# DPT2_0.net
KiCad netlist of a schematic drawn in Altium Designer
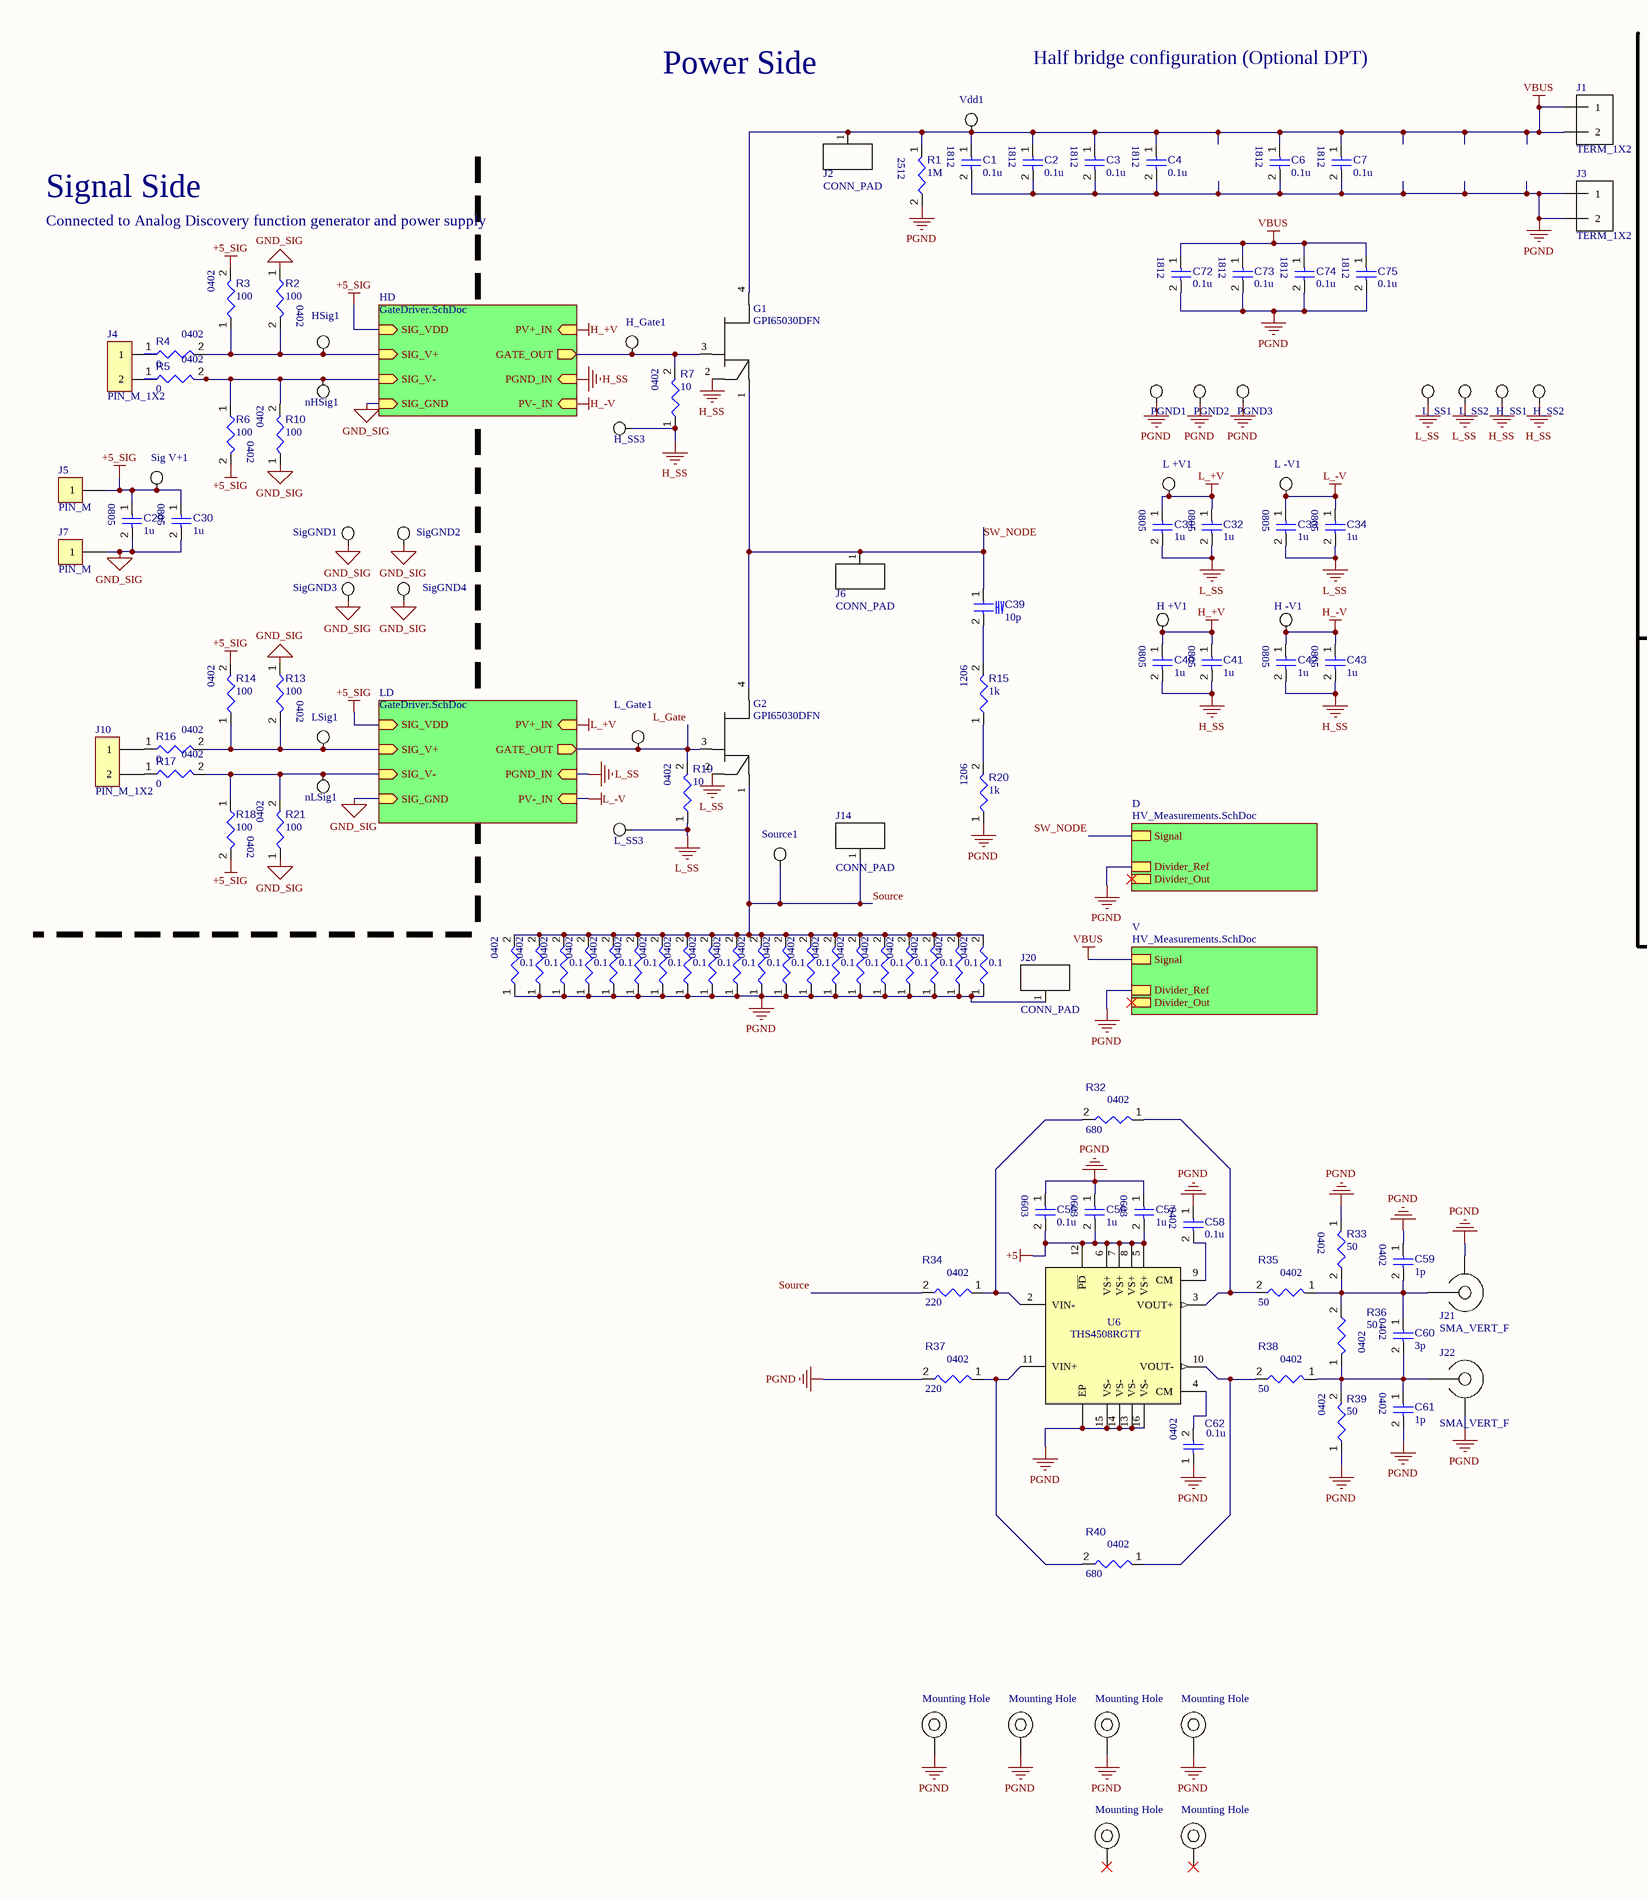
[diagram p0: DPT2.0.SchDoc, left]
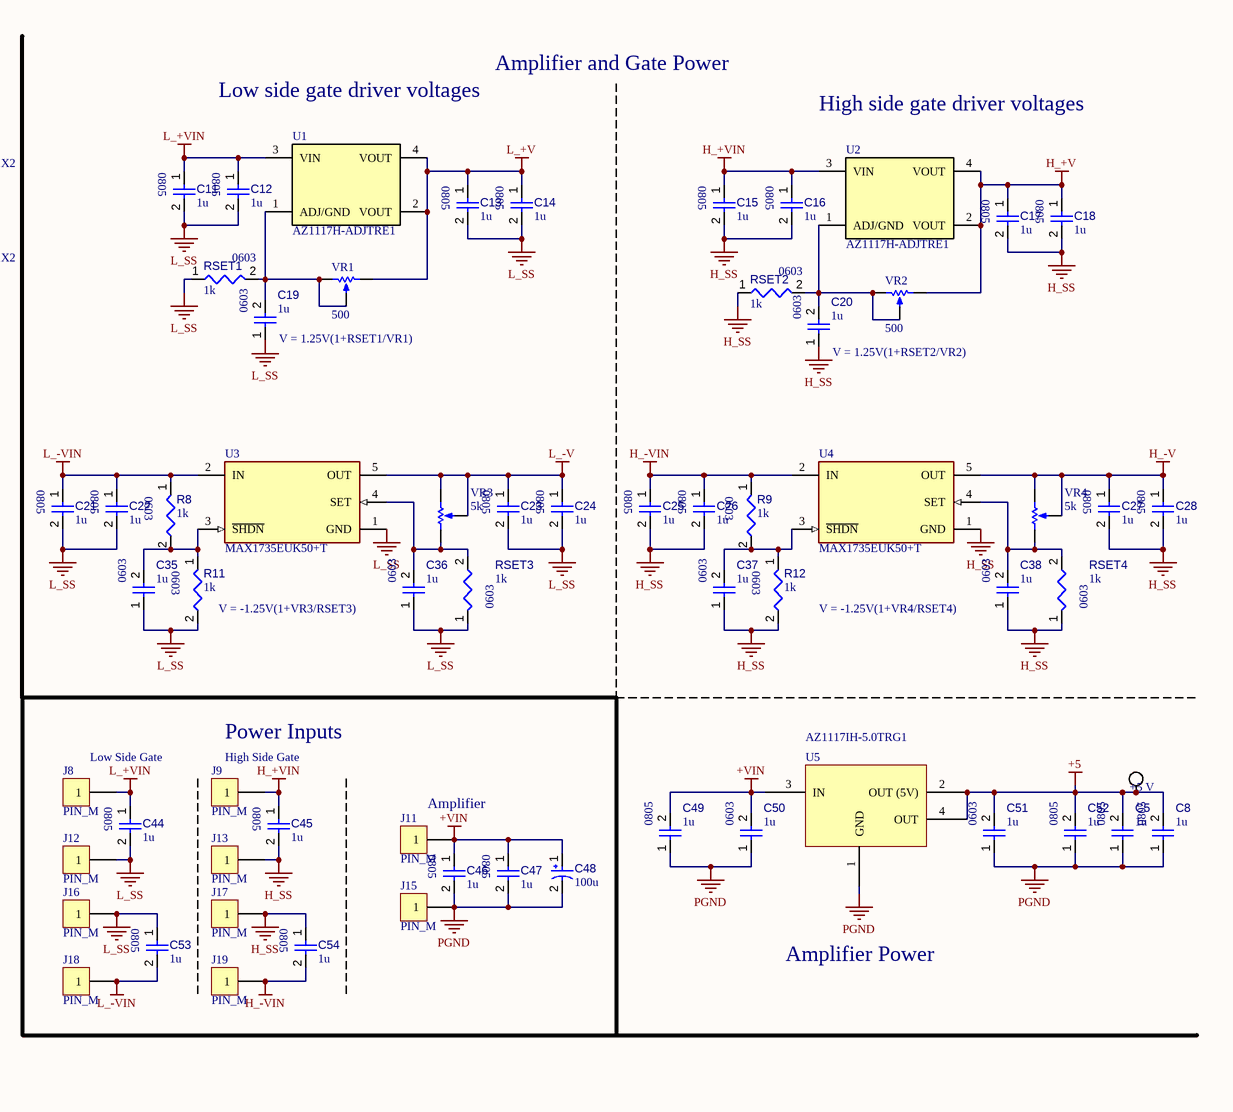
[diagram p1: DPT2.0.SchDoc, right]

(export (version "E")
  (design (tool "Eeschema 10.0.6"))
  (components
    (comp (ref "+5 V")
      (value "Testpoint")
      (footprint "Testpoint-Footprint-1")
      (description "testpoint for circuit")
      (libsource (lib "2256-GaN Power") (part "Testpoint-Symbol-1"))
    )
    (comp (ref "C1")
      (value "0.1u")
      (footprint "CAP_1812")
      (description "Non polarized SMD capacitor - 1812 (4532 Metric)")
      (fields (field (name "Comment") "CAP-1812"))
      (libsource (lib "2256-GaN Power") (part "CAP-NP-2"))
    )
    (comp (ref "C2")
      (value "0.1u")
      (footprint "CAP_1812")
      (description "Non polarized SMD capacitor - 1812 (4532 Metric)")
      (fields (field (name "Comment") "CAP-1812"))
      (libsource (lib "2256-GaN Power") (part "CAP-NP-2"))
    )
    (comp (ref "C3")
      (value "0.1u")
      (footprint "CAP_1812")
      (description "Non polarized SMD capacitor - 1812 (4532 Metric)")
      (fields (field (name "Comment") "CAP-1812"))
      (libsource (lib "2256-GaN Power") (part "CAP-NP-2"))
    )
    (comp (ref "C4")
      (value "0.1u")
      (footprint "CAP_1812")
      (description "Non polarized SMD capacitor - 1812 (4532 Metric)")
      (fields (field (name "Comment") "CAP-1812"))
      (libsource (lib "2256-GaN Power") (part "CAP-NP-2"))
    )
    (comp (ref "C5")
      (value "1u")
      (footprint "CAP_0805_MED")
      (description "Non polarized SMD capacitor - 0805 (1608 Metric)")
      (fields (field (name "Comment") "CAP-0805"))
      (libsource (lib "2256-GaN Power") (part "CAP-NP-2"))
    )
    (comp (ref "C6")
      (value "0.1u")
      (footprint "CAP_1812")
      (description "Non polarized SMD capacitor - 1812 (4532 Metric)")
      (fields (field (name "Comment") "CAP-1812"))
      (libsource (lib "2256-GaN Power") (part "CAP-NP-2"))
    )
    (comp (ref "C7")
      (value "0.1u")
      (footprint "CAP_1812")
      (description "Non polarized SMD capacitor - 1812 (4532 Metric)")
      (fields (field (name "Comment") "CAP-1812"))
      (libsource (lib "2256-GaN Power") (part "CAP-NP-2"))
    )
    (comp (ref "C8")
      (value "1u")
      (footprint "CAP_0805_MED")
      (description "Non polarized SMD capacitor - 0805 (1608 Metric)")
      (fields (field (name "Comment") "CAP-0805"))
      (libsource (lib "2256-GaN Power") (part "CAP-NP-2"))
    )
    (comp (ref "C11")
      (value "1u")
      (footprint "CAP_0805_MED")
      (description "Non polarized SMD capacitor - 0805 (1608 Metric)")
      (fields (field (name "Comment") "CAP-0805"))
      (libsource (lib "2256-GaN Power") (part "CAP-NP-2"))
    )
    (comp (ref "C12")
      (value "1u")
      (footprint "CAP_0805_MED")
      (description "Non polarized SMD capacitor - 0805 (1608 Metric)")
      (fields (field (name "Comment") "CAP-0805"))
      (libsource (lib "2256-GaN Power") (part "CAP-NP-2"))
    )
    (comp (ref "C13")
      (value "1u")
      (footprint "CAP_0805_MED")
      (description "Non polarized SMD capacitor - 0805 (1608 Metric)")
      (fields (field (name "Comment") "CAP-0805"))
      (libsource (lib "2256-GaN Power") (part "CAP-NP-2"))
    )
    (comp (ref "C14")
      (value "1u")
      (footprint "CAP_0805_MED")
      (description "Non polarized SMD capacitor - 0805 (1608 Metric)")
      (fields (field (name "Comment") "CAP-0805"))
      (libsource (lib "2256-GaN Power") (part "CAP-NP-2"))
    )
    (comp (ref "C15")
      (value "1u")
      (footprint "CAP_0805_MED")
      (description "Non polarized SMD capacitor - 0805 (1608 Metric)")
      (fields (field (name "Comment") "CAP-0805"))
      (libsource (lib "2256-GaN Power") (part "CAP-NP-2"))
    )
    (comp (ref "C16")
      (value "1u")
      (footprint "CAP_0805_MED")
      (description "Non polarized SMD capacitor - 0805 (1608 Metric)")
      (fields (field (name "Comment") "CAP-0805"))
      (libsource (lib "2256-GaN Power") (part "CAP-NP-2"))
    )
    (comp (ref "C17")
      (value "1u")
      (footprint "CAP_0805_MED")
      (description "Non polarized SMD capacitor - 0805 (1608 Metric)")
      (fields (field (name "Comment") "CAP-0805"))
      (libsource (lib "2256-GaN Power") (part "CAP-NP-2"))
    )
    (comp (ref "C18")
      (value "1u")
      (footprint "CAP_0805_MED")
      (description "Non polarized SMD capacitor - 0805 (1608 Metric)")
      (fields (field (name "Comment") "CAP-0805"))
      (libsource (lib "2256-GaN Power") (part "CAP-NP-2"))
    )
    (comp (ref "C19")
      (value "1u")
      (footprint "CAP_0603_HIGH")
      (description "Non polarized SMD capacitor - 0603 (1608 Metric)")
      (fields (field (name "Comment") "CAP-0603"))
      (libsource (lib "2256-GaN Power") (part "CAP-NP-2"))
    )
    (comp (ref "C20")
      (value "1u")
      (footprint "CAP_0603_HIGH")
      (description "Non polarized SMD capacitor - 0603 (1608 Metric)")
      (fields (field (name "Comment") "CAP-0603"))
      (libsource (lib "2256-GaN Power") (part "CAP-NP-2"))
    )
    (comp (ref "C21")
      (value "1u")
      (footprint "CAP_0805_MED")
      (description "Non polarized SMD capacitor - 0805 (1608 Metric)")
      (fields (field (name "Comment") "CAP-0805"))
      (libsource (lib "2256-GaN Power") (part "CAP-NP-2"))
    )
    (comp (ref "C22")
      (value "1u")
      (footprint "CAP_0805_MED")
      (description "Non polarized SMD capacitor - 0805 (1608 Metric)")
      (fields (field (name "Comment") "CAP-0805"))
      (libsource (lib "2256-GaN Power") (part "CAP-NP-2"))
    )
    (comp (ref "C23")
      (value "1u")
      (footprint "CAP_0805_MED")
      (description "Non polarized SMD capacitor - 0805 (1608 Metric)")
      (fields (field (name "Comment") "CAP-0805"))
      (libsource (lib "2256-GaN Power") (part "CAP-NP-2"))
    )
    (comp (ref "C24")
      (value "1u")
      (footprint "CAP_0805_MED")
      (description "Non polarized SMD capacitor - 0805 (1608 Metric)")
      (fields (field (name "Comment") "CAP-0805"))
      (libsource (lib "2256-GaN Power") (part "CAP-NP-2"))
    )
    (comp (ref "C25")
      (value "1u")
      (footprint "CAP_0805_MED")
      (description "Non polarized SMD capacitor - 0805 (1608 Metric)")
      (fields (field (name "Comment") "CAP-0805"))
      (libsource (lib "2256-GaN Power") (part "CAP-NP-2"))
    )
    (comp (ref "C26")
      (value "1u")
      (footprint "CAP_0805_MED")
      (description "Non polarized SMD capacitor - 0805 (1608 Metric)")
      (fields (field (name "Comment") "CAP-0805"))
      (libsource (lib "2256-GaN Power") (part "CAP-NP-2"))
    )
    (comp (ref "C27")
      (value "1u")
      (footprint "CAP_0805_MED")
      (description "Non polarized SMD capacitor - 0805 (1608 Metric)")
      (fields (field (name "Comment") "CAP-0805"))
      (libsource (lib "2256-GaN Power") (part "CAP-NP-2"))
    )
    (comp (ref "C28")
      (value "1u")
      (footprint "CAP_0805_MED")
      (description "Non polarized SMD capacitor - 0805 (1608 Metric)")
      (fields (field (name "Comment") "CAP-0805"))
      (libsource (lib "2256-GaN Power") (part "CAP-NP-2"))
    )
    (comp (ref "C29")
      (value "1u")
      (footprint "CAP_0805_MED")
      (description "Non polarized SMD capacitor - 0805 (1608 Metric)")
      (fields (field (name "Comment") "CAP-0805"))
      (libsource (lib "2256-GaN Power") (part "CAP-NP-2"))
    )
    (comp (ref "C30")
      (value "1u")
      (footprint "CAP_0805_MED")
      (description "Non polarized SMD capacitor - 0805 (1608 Metric)")
      (fields (field (name "Comment") "CAP-0805"))
      (libsource (lib "2256-GaN Power") (part "CAP-NP-2"))
    )
    (comp (ref "C31")
      (value "1u")
      (footprint "CAP_0805_MED")
      (description "Non polarized SMD capacitor - 0805 (1608 Metric)")
      (fields (field (name "Comment") "CAP-0805"))
      (libsource (lib "2256-GaN Power") (part "CAP-NP-2"))
    )
    (comp (ref "C32")
      (value "1u")
      (footprint "CAP_0805_MED")
      (description "Non polarized SMD capacitor - 0805 (1608 Metric)")
      (fields (field (name "Comment") "CAP-0805"))
      (libsource (lib "2256-GaN Power") (part "CAP-NP-2"))
    )
    (comp (ref "C33")
      (value "1u")
      (footprint "CAP_0805_MED")
      (description "Non polarized SMD capacitor - 0805 (1608 Metric)")
      (fields (field (name "Comment") "CAP-0805"))
      (libsource (lib "2256-GaN Power") (part "CAP-NP-2"))
    )
    (comp (ref "C34")
      (value "1u")
      (footprint "CAP_0805_MED")
      (description "Non polarized SMD capacitor - 0805 (1608 Metric)")
      (fields (field (name "Comment") "CAP-0805"))
      (libsource (lib "2256-GaN Power") (part "CAP-NP-2"))
    )
    (comp (ref "C35")
      (value "1u")
      (footprint "CAP_0603_HIGH")
      (description "Non polarized SMD capacitor - 0603 (1608 Metric)")
      (fields (field (name "Comment") "CAP-0603"))
      (libsource (lib "2256-GaN Power") (part "CAP-NP-2"))
    )
    (comp (ref "C36")
      (value "1u")
      (footprint "CAP_0603_HIGH")
      (description "Non polarized SMD capacitor - 0603 (1608 Metric)")
      (fields (field (name "Comment") "CAP-0603"))
      (libsource (lib "2256-GaN Power") (part "CAP-NP-2"))
    )
    (comp (ref "C37")
      (value "1u")
      (footprint "CAP_0603_HIGH")
      (description "Non polarized SMD capacitor - 0603 (1608 Metric)")
      (fields (field (name "Comment") "CAP-0603"))
      (libsource (lib "2256-GaN Power") (part "CAP-NP-2"))
    )
    (comp (ref "C38")
      (value "1u")
      (footprint "CAP_0603_HIGH")
      (description "Non polarized SMD capacitor - 0603 (1608 Metric)")
      (fields (field (name "Comment") "CAP-0603"))
      (libsource (lib "2256-GaN Power") (part "CAP-NP-2"))
    )
    (comp (ref "C39")
      (value "10p")
      (footprint "CAP_1206_HV")
      (description "Non polarized SMD capacitor - 1206 (3216 Metric) High Voltage")
      (fields (field (name "Comment") "CAP-1206-HV"))
      (libsource (lib "2256-GaN Power") (part "CAP-NP-2-HV"))
    )
    (comp (ref "C40")
      (value "1u")
      (footprint "CAP_0805_MED")
      (description "Non polarized SMD capacitor - 0805 (1608 Metric)")
      (fields (field (name "Comment") "CAP-0805"))
      (libsource (lib "2256-GaN Power") (part "CAP-NP-2"))
    )
    (comp (ref "C41")
      (value "1u")
      (footprint "CAP_0805_MED")
      (description "Non polarized SMD capacitor - 0805 (1608 Metric)")
      (fields (field (name "Comment") "CAP-0805"))
      (libsource (lib "2256-GaN Power") (part "CAP-NP-2"))
    )
    (comp (ref "C42")
      (value "1u")
      (footprint "CAP_0805_MED")
      (description "Non polarized SMD capacitor - 0805 (1608 Metric)")
      (fields (field (name "Comment") "CAP-0805"))
      (libsource (lib "2256-GaN Power") (part "CAP-NP-2"))
    )
    (comp (ref "C43")
      (value "1u")
      (footprint "CAP_0805_MED")
      (description "Non polarized SMD capacitor - 0805 (1608 Metric)")
      (fields (field (name "Comment") "CAP-0805"))
      (libsource (lib "2256-GaN Power") (part "CAP-NP-2"))
    )
    (comp (ref "C44")
      (value "1u")
      (footprint "CAP_0805_MED")
      (description "Non polarized SMD capacitor - 0805 (1608 Metric)")
      (fields (field (name "Comment") "CAP-0805"))
      (libsource (lib "2256-GaN Power") (part "CAP-NP-2"))
    )
    (comp (ref "C45")
      (value "1u")
      (footprint "CAP_0805_MED")
      (description "Non polarized SMD capacitor - 0805 (1608 Metric)")
      (fields (field (name "Comment") "CAP-0805"))
      (libsource (lib "2256-GaN Power") (part "CAP-NP-2"))
    )
    (comp (ref "C46")
      (value "1u")
      (footprint "CAP_0805_MED")
      (description "Non polarized SMD capacitor - 0805 (1608 Metric)")
      (fields (field (name "Comment") "CAP-0805"))
      (libsource (lib "2256-GaN Power") (part "CAP-NP-2"))
    )
    (comp (ref "C47")
      (value "1u")
      (footprint "CAP_0805_MED")
      (description "Non polarized SMD capacitor - 0805 (1608 Metric)")
      (fields (field (name "Comment") "CAP-0805"))
      (libsource (lib "2256-GaN Power") (part "CAP-NP-2"))
    )
    (comp (ref "C48")
      (value "100u")
      (footprint "PCAP_2MM_5MM")
      (description "Polarized THT capacitor - Radial can, 2mm lead spacing, 5mm diameter")
      (fields (field (name "Comment") "PCAP-2MMx5MM"))
      (libsource (lib "2256-GaN Power") (part "CAP-P-2"))
    )
    (comp (ref "C49")
      (value "1u")
      (footprint "CAP_0805_MED")
      (description "Non polarized SMD capacitor - 0805 (1608 Metric)")
      (fields (field (name "Comment") "CAP-0805"))
      (libsource (lib "2256-GaN Power") (part "CAP-NP-2"))
    )
    (comp (ref "C50")
      (value "1u")
      (footprint "CAP_0603_HIGH")
      (description "Non polarized SMD capacitor - 0603 (1608 Metric)")
      (fields (field (name "Comment") "CAP-0603"))
      (libsource (lib "2256-GaN Power") (part "CAP-NP-2"))
    )
    (comp (ref "C51")
      (value "1u")
      (footprint "CAP_0603_HIGH")
      (description "Non polarized SMD capacitor - 0603 (1608 Metric)")
      (fields (field (name "Comment") "CAP-0603"))
      (libsource (lib "2256-GaN Power") (part "CAP-NP-2"))
    )
    (comp (ref "C52")
      (value "1u")
      (footprint "CAP_0805_MED")
      (description "Non polarized SMD capacitor - 0805 (1608 Metric)")
      (fields (field (name "Comment") "CAP-0805"))
      (libsource (lib "2256-GaN Power") (part "CAP-NP-2"))
    )
    (comp (ref "C53")
      (value "1u")
      (footprint "CAP_0805_MED")
      (description "Non polarized SMD capacitor - 0805 (1608 Metric)")
      (fields (field (name "Comment") "CAP-0805"))
      (libsource (lib "2256-GaN Power") (part "CAP-NP-2"))
    )
    (comp (ref "C54")
      (value "1u")
      (footprint "CAP_0805_MED")
      (description "Non polarized SMD capacitor - 0805 (1608 Metric)")
      (fields (field (name "Comment") "CAP-0805"))
      (libsource (lib "2256-GaN Power") (part "CAP-NP-2"))
    )
    (comp (ref "C55")
      (value "0.1u")
      (footprint "CAP_0603_HIGH")
      (description "Non polarized SMD capacitor - 0603 (1608 Metric)")
      (fields (field (name "Comment") "CAP-0603"))
      (libsource (lib "2256-GaN Power") (part "CAP-NP-2"))
    )
    (comp (ref "C56")
      (value "1u")
      (footprint "CAP_0603_HIGH")
      (description "Non polarized SMD capacitor - 0603 (1608 Metric)")
      (fields (field (name "Comment") "CAP-0603"))
      (libsource (lib "2256-GaN Power") (part "CAP-NP-2"))
    )
    (comp (ref "C57")
      (value "1u")
      (footprint "CAP_0603_HIGH")
      (description "Non polarized SMD capacitor - 0603 (1608 Metric)")
      (fields (field (name "Comment") "CAP-0603"))
      (libsource (lib "2256-GaN Power") (part "CAP-NP-2"))
    )
    (comp (ref "C58")
      (value "0.1u")
      (footprint "CAP_0402_HIGH")
      (description "Non polarized SMD capacitor - 0402 (1005 Metric)")
      (fields (field (name "Comment") "CAP-0402"))
      (libsource (lib "2256-GaN Power") (part "CAP-NP-2"))
    )
    (comp (ref "C59")
      (value "1p")
      (footprint "CAP_0402_HIGH")
      (description "Non polarized SMD capacitor - 0402 (1005 Metric)")
      (fields (field (name "Comment") "CAP-0402"))
      (libsource (lib "2256-GaN Power") (part "CAP-NP-2"))
    )
    (comp (ref "C60")
      (value "3p")
      (footprint "CAP_0402_HIGH")
      (description "Non polarized SMD capacitor - 0402 (1005 Metric)")
      (fields (field (name "Comment") "CAP-0402"))
      (libsource (lib "2256-GaN Power") (part "CAP-NP-2"))
    )
    (comp (ref "C61")
      (value "1p")
      (footprint "CAP_0402_HIGH")
      (description "Non polarized SMD capacitor - 0402 (1005 Metric)")
      (fields (field (name "Comment") "CAP-0402"))
      (libsource (lib "2256-GaN Power") (part "CAP-NP-2"))
    )
    (comp (ref "C62")
      (value "0.1u")
      (footprint "CAP_0402_HIGH")
      (description "Non polarized SMD capacitor - 0402 (1005 Metric)")
      (fields (field (name "Comment") "CAP-0402"))
      (libsource (lib "2256-GaN Power") (part "CAP-NP-2"))
    )
    (comp (ref "C72")
      (value "0.1u")
      (footprint "CAP_1812")
      (description "Non polarized SMD capacitor - 1812 (4532 Metric)")
      (fields (field (name "Comment") "CAP-1812"))
      (libsource (lib "2256-GaN Power") (part "CAP-NP-2"))
    )
    (comp (ref "C73")
      (value "0.1u")
      (footprint "CAP_1812")
      (description "Non polarized SMD capacitor - 1812 (4532 Metric)")
      (fields (field (name "Comment") "CAP-1812"))
      (libsource (lib "2256-GaN Power") (part "CAP-NP-2"))
    )
    (comp (ref "C74")
      (value "0.1u")
      (footprint "CAP_1812")
      (description "Non polarized SMD capacitor - 1812 (4532 Metric)")
      (fields (field (name "Comment") "CAP-1812"))
      (libsource (lib "2256-GaN Power") (part "CAP-NP-2"))
    )
    (comp (ref "C75")
      (value "0.1u")
      (footprint "CAP_1812")
      (description "Non polarized SMD capacitor - 1812 (4532 Metric)")
      (fields (field (name "Comment") "CAP-1812"))
      (libsource (lib "2256-GaN Power") (part "CAP-NP-2"))
    )
    (comp (ref "G1")
      (value "GPI65030DFN")
      (footprint "DFN_8X8")
      (description "650V 15A GaN Enhancement mode Transistor")
      (libsource (lib "2256-GaN Power") (part "TRANS_GPI65030DFN"))
    )
    (comp (ref "G2")
      (value "GPI65030DFN")
      (footprint "DFN_8X8")
      (description "650V 15A GaN Enhancement mode Transistor")
      (libsource (lib "2256-GaN Power") (part "TRANS_GPI65030DFN"))
    )
    (comp (ref "H +V1")
      (value "Testpoint")
      (footprint "Testpoint-Footprint-1")
      (description "testpoint for circuit")
      (libsource (lib "2256-GaN Power") (part "Testpoint-Symbol-1"))
    )
    (comp (ref "H -V1")
      (value "Testpoint")
      (footprint "Testpoint-Footprint-1")
      (description "testpoint for circuit")
      (libsource (lib "2256-GaN Power") (part "Testpoint-Symbol-1"))
    )
    (comp (ref "HSig1")
      (value "Testpoint")
      (footprint "Testpoint-Footprint-1")
      (description "testpoint for circuit")
      (libsource (lib "2256-GaN Power") (part "Testpoint-Symbol-1"))
    )
    (comp (ref "H_Gate1")
      (value "Testpoint")
      (footprint "Testpoint-Footprint-1")
      (description "testpoint for circuit")
      (libsource (lib "2256-GaN Power") (part "Testpoint-Symbol-1"))
    )
    (comp (ref "H_SS1")
      (value "Testpoint")
      (footprint "Testpoint-Footprint-1")
      (description "testpoint for circuit")
      (libsource (lib "2256-GaN Power") (part "Testpoint-Symbol-1"))
    )
    (comp (ref "H_SS2")
      (value "Testpoint")
      (footprint "Testpoint-Footprint-1")
      (description "testpoint for circuit")
      (libsource (lib "2256-GaN Power") (part "Testpoint-Symbol-1"))
    )
    (comp (ref "H_SS3")
      (value "Testpoint")
      (footprint "Testpoint-Footprint-1")
      (description "testpoint for circuit")
      (libsource (lib "2256-GaN Power") (part "Testpoint-Symbol-1"))
    )
    (comp (ref "J1")
      (value "TERM_1X2")
      (footprint "J_TERM_BLK_1X2")
      (description "Terminal Block 1X2, 6.35mm pitch")
      (libsource (lib "2256-GaN Power") (part "TERM_BLK_1X2"))
    )
    (comp (ref "J2")
      (value "CONN_PAD")
      (footprint "CONN_PAD")
      (description "Solderable Connection Pad")
      (libsource (lib "2256-GaN Power") (part "CONN_PAD"))
    )
    (comp (ref "J3")
      (value "TERM_1X2")
      (footprint "J_TERM_BLK_1X2")
      (description "Terminal Block 1X2, 6.35mm pitch")
      (libsource (lib "2256-GaN Power") (part "TERM_BLK_1X2"))
    )
    (comp (ref "J4")
      (value "PIN_M_1X2")
      (footprint "J_THT_2.54MM_1X2")
      (description "Male Pin 2.54mm pitch 1X2")
      (libsource (lib "2256-GaN Power") (part "M_PIN_HEAD_1X2"))
    )
    (comp (ref "J5")
      (value "PIN_M")
      (footprint "J_THT_1_PIN")
      (description "Male Pin, 1 Pin")
      (libsource (lib "2256-GaN Power") (part "M_PIN_HEAD_1X1"))
    )
    (comp (ref "J6")
      (value "CONN_PAD")
      (footprint "CONN_PAD")
      (description "Solderable Connection Pad")
      (libsource (lib "2256-GaN Power") (part "CONN_PAD"))
    )
    (comp (ref "J7")
      (value "PIN_M")
      (footprint "J_THT_1_PIN")
      (description "Male Pin, 1 Pin")
      (libsource (lib "2256-GaN Power") (part "M_PIN_HEAD_1X1"))
    )
    (comp (ref "J8")
      (value "PIN_M")
      (footprint "J_THT_1_PIN")
      (description "Male Pin, 1 Pin")
      (libsource (lib "2256-GaN Power") (part "M_PIN_HEAD_1X1"))
    )
    (comp (ref "J9")
      (value "PIN_M")
      (footprint "J_THT_1_PIN")
      (description "Male Pin, 1 Pin")
      (libsource (lib "2256-GaN Power") (part "M_PIN_HEAD_1X1"))
    )
    (comp (ref "J10")
      (value "PIN_M_1X2")
      (footprint "J_THT_2.54MM_1X2")
      (description "Male Pin 2.54mm pitch 1X2")
      (libsource (lib "2256-GaN Power") (part "M_PIN_HEAD_1X2"))
    )
    (comp (ref "J11")
      (value "PIN_M")
      (footprint "J_THT_1_PIN")
      (description "Male Pin, 1 Pin")
      (libsource (lib "2256-GaN Power") (part "M_PIN_HEAD_1X1"))
    )
    (comp (ref "J12")
      (value "PIN_M")
      (footprint "J_THT_1_PIN")
      (description "Male Pin, 1 Pin")
      (libsource (lib "2256-GaN Power") (part "M_PIN_HEAD_1X1"))
    )
    (comp (ref "J13")
      (value "PIN_M")
      (footprint "J_THT_1_PIN")
      (description "Male Pin, 1 Pin")
      (libsource (lib "2256-GaN Power") (part "M_PIN_HEAD_1X1"))
    )
    (comp (ref "J14")
      (value "CONN_PAD")
      (footprint "CONN_PAD")
      (description "Solderable Connection Pad")
      (libsource (lib "") (part "CONN_PAD_1"))
    )
    (comp (ref "J15")
      (value "PIN_M")
      (footprint "J_THT_1_PIN")
      (description "Male Pin, 1 Pin")
      (libsource (lib "2256-GaN Power") (part "M_PIN_HEAD_1X1"))
    )
    (comp (ref "J16")
      (value "PIN_M")
      (footprint "J_THT_1_PIN")
      (description "Male Pin, 1 Pin")
      (libsource (lib "2256-GaN Power") (part "M_PIN_HEAD_1X1"))
    )
    (comp (ref "J17")
      (value "PIN_M")
      (footprint "J_THT_1_PIN")
      (description "Male Pin, 1 Pin")
      (libsource (lib "2256-GaN Power") (part "M_PIN_HEAD_1X1"))
    )
    (comp (ref "J18")
      (value "PIN_M")
      (footprint "J_THT_1_PIN")
      (description "Male Pin, 1 Pin")
      (libsource (lib "2256-GaN Power") (part "M_PIN_HEAD_1X1"))
    )
    (comp (ref "J19")
      (value "PIN_M")
      (footprint "J_THT_1_PIN")
      (description "Male Pin, 1 Pin")
      (libsource (lib "2256-GaN Power") (part "M_PIN_HEAD_1X1"))
    )
    (comp (ref "J20")
      (value "CONN_PAD")
      (footprint "CONN_PAD")
      (description "Solderable Connection Pad")
      (libsource (lib "") (part "CONN_PAD_1"))
    )
    (comp (ref "J21")
      (value "SMA_VERT_F")
      (footprint "SMA_VERT_F")
      (description "SMA connector, Vertical, Female")
      (libsource (lib "") (part "SMA_F_1"))
    )
    (comp (ref "J22")
      (value "SMA_VERT_F")
      (footprint "SMA_VERT_F")
      (description "SMA connector, Vertical, Female")
      (libsource (lib "2256-GaN Power") (part "SMA_F"))
    )
    (comp (ref "L +V1")
      (value "Testpoint")
      (footprint "Testpoint-Footprint-1")
      (description "testpoint for circuit")
      (libsource (lib "2256-GaN Power") (part "Testpoint-Symbol-1"))
    )
    (comp (ref "L -V1")
      (value "Testpoint")
      (footprint "Testpoint-Footprint-1")
      (description "testpoint for circuit")
      (libsource (lib "2256-GaN Power") (part "Testpoint-Symbol-1"))
    )
    (comp (ref "LSig1")
      (value "Testpoint")
      (footprint "Testpoint-Footprint-1")
      (description "testpoint for circuit")
      (libsource (lib "2256-GaN Power") (part "Testpoint-Symbol-1"))
    )
    (comp (ref "L_Gate1")
      (value "Testpoint")
      (footprint "Testpoint-Footprint-1")
      (description "testpoint for circuit")
      (libsource (lib "2256-GaN Power") (part "Testpoint-Symbol-1"))
    )
    (comp (ref "L_SS1")
      (value "Testpoint")
      (footprint "Testpoint-Footprint-1")
      (description "testpoint for circuit")
      (libsource (lib "2256-GaN Power") (part "Testpoint-Symbol-1"))
    )
    (comp (ref "L_SS2")
      (value "Testpoint")
      (footprint "Testpoint-Footprint-1")
      (description "testpoint for circuit")
      (libsource (lib "2256-GaN Power") (part "Testpoint-Symbol-1"))
    )
    (comp (ref "L_SS3")
      (value "Testpoint")
      (footprint "Testpoint-Footprint-1")
      (description "testpoint for circuit")
      (libsource (lib "2256-GaN Power") (part "Testpoint-Symbol-1"))
    )
    (comp (ref "MH1")
      (value "Mounting Hole")
      (footprint "Mounting Hole-Footprint-1")
      (libsource (lib "2256-GaN Power") (part "Mounting Hole-Symbol-1"))
    )
    (comp (ref "MH2")
      (value "Mounting Hole")
      (footprint "Mounting Hole-Footprint-1")
      (libsource (lib "2256-GaN Power") (part "Mounting Hole-Symbol-1"))
    )
    (comp (ref "MH3")
      (value "Mounting Hole")
      (footprint "Mounting Hole-Footprint-1")
      (libsource (lib "2256-GaN Power") (part "Mounting Hole-Symbol-1"))
    )
    (comp (ref "MH4")
      (value "Mounting Hole")
      (footprint "Mounting Hole-Footprint-1")
      (libsource (lib "2256-GaN Power") (part "Mounting Hole-Symbol-1"))
    )
    (comp (ref "MH7")
      (value "Mounting Hole")
      (footprint "Mounting Hole-Footprint-1")
      (libsource (lib "2256-GaN Power") (part "Mounting Hole-Symbol-1"))
    )
    (comp (ref "MH8")
      (value "Mounting Hole")
      (footprint "Mounting Hole-Footprint-1")
      (libsource (lib "2256-GaN Power") (part "Mounting Hole-Symbol-1"))
    )
    (comp (ref "nHSig1")
      (value "Testpoint")
      (footprint "Testpoint-Footprint-1")
      (description "testpoint for circuit")
      (libsource (lib "2256-GaN Power") (part "Testpoint-Symbol-1"))
    )
    (comp (ref "nLSig1")
      (value "Testpoint")
      (footprint "Testpoint-Footprint-1")
      (description "testpoint for circuit")
      (libsource (lib "2256-GaN Power") (part "Testpoint-Symbol-1"))
    )
    (comp (ref "PGND1")
      (value "Testpoint")
      (footprint "Testpoint-Footprint-1")
      (description "testpoint for circuit")
      (libsource (lib "2256-GaN Power") (part "Testpoint-Symbol-1"))
    )
    (comp (ref "PGND2")
      (value "Testpoint")
      (footprint "Testpoint-Footprint-1")
      (description "testpoint for circuit")
      (libsource (lib "2256-GaN Power") (part "Testpoint-Symbol-1"))
    )
    (comp (ref "PGND3")
      (value "Testpoint")
      (footprint "Testpoint-Footprint-1")
      (description "testpoint for circuit")
      (libsource (lib "2256-GaN Power") (part "Testpoint-Symbol-1"))
    )
    (comp (ref "R1")
      (value "1M")
      (footprint "RES_2512_MED")
      (description "SMD Resistor - 2512 (6432 Metric)")
      (fields (field (name "Comment") "RES-2512"))
      (libsource (lib "2256-GaN Power") (part "RES-2"))
    )
    (comp (ref "R2")
      (value "100")
      (footprint "RES_0402_HIGH")
      (description "SMD Resistor - 0402 (1005 Metric)")
      (fields (field (name "Comment") "RES-0402"))
      (libsource (lib "2256-GaN Power") (part "RES-2"))
    )
    (comp (ref "R3")
      (value "100")
      (footprint "RES_0402_HIGH")
      (description "SMD Resistor - 0402 (1005 Metric)")
      (fields (field (name "Comment") "RES-0402"))
      (libsource (lib "2256-GaN Power") (part "RES-2"))
    )
    (comp (ref "R4")
      (value "0")
      (footprint "RES_0402_HIGH")
      (description "SMD Resistor - 0402 (1005 Metric)")
      (fields (field (name "Comment") "RES-0402"))
      (libsource (lib "2256-GaN Power") (part "RES-2"))
    )
    (comp (ref "R5")
      (value "0")
      (footprint "RES_0402_HIGH")
      (description "SMD Resistor - 0402 (1005 Metric)")
      (fields (field (name "Comment") "RES-0402"))
      (libsource (lib "2256-GaN Power") (part "RES-2"))
    )
    (comp (ref "R6")
      (value "100")
      (footprint "RES_0402_HIGH")
      (description "SMD Resistor - 0402 (1005 Metric)")
      (fields (field (name "Comment") "RES-0402"))
      (libsource (lib "2256-GaN Power") (part "RES-2"))
    )
    (comp (ref "R7")
      (value "10")
      (footprint "RES_0402_HIGH")
      (description "SMD Resistor - 0402 (1005 Metric)")
      (fields (field (name "Comment") "RES-0402"))
      (libsource (lib "2256-GaN Power") (part "RES-2"))
    )
    (comp (ref "R8")
      (value "1k")
      (footprint "RES_0603_MED")
      (description "SMD Resistor - 0603 (1608 Metric)")
      (fields (field (name "Comment") "RES-0603"))
      (libsource (lib "2256-GaN Power") (part "RES-2"))
    )
    (comp (ref "R9")
      (value "1k")
      (footprint "RES_0603_MED")
      (description "SMD Resistor - 0603 (1608 Metric)")
      (fields (field (name "Comment") "RES-0603"))
      (libsource (lib "2256-GaN Power") (part "RES-2"))
    )
    (comp (ref "R10")
      (value "100")
      (footprint "RES_0402_HIGH")
      (description "SMD Resistor - 0402 (1005 Metric)")
      (fields (field (name "Comment") "RES-0402"))
      (libsource (lib "2256-GaN Power") (part "RES-2"))
    )
    (comp (ref "R11")
      (value "1k")
      (footprint "RES_0603_MED")
      (description "SMD Resistor - 0603 (1608 Metric)")
      (fields (field (name "Comment") "RES-0603"))
      (libsource (lib "2256-GaN Power") (part "RES-2"))
    )
    (comp (ref "R12")
      (value "1k")
      (footprint "RES_0603_MED")
      (description "SMD Resistor - 0603 (1608 Metric)")
      (fields (field (name "Comment") "RES-0603"))
      (libsource (lib "2256-GaN Power") (part "RES-2"))
    )
    (comp (ref "R13")
      (value "100")
      (footprint "RES_0402_HIGH")
      (description "SMD Resistor - 0402 (1005 Metric)")
      (fields (field (name "Comment") "RES-0402"))
      (libsource (lib "2256-GaN Power") (part "RES-2"))
    )
    (comp (ref "R14")
      (value "100")
      (footprint "RES_0402_HIGH")
      (description "SMD Resistor - 0402 (1005 Metric)")
      (fields (field (name "Comment") "RES-0402"))
      (libsource (lib "2256-GaN Power") (part "RES-2"))
    )
    (comp (ref "R15")
      (value "1k")
      (footprint "RES_1206_MED")
      (description "SMD Resistor - 1206 (3216 Metric)")
      (fields (field (name "Comment") "RES-1206"))
      (libsource (lib "2256-GaN Power") (part "RES-2"))
    )
    (comp (ref "R16")
      (value "0")
      (footprint "RES_0402_HIGH")
      (description "SMD Resistor - 0402 (1005 Metric)")
      (fields (field (name "Comment") "RES-0402"))
      (libsource (lib "2256-GaN Power") (part "RES-2"))
    )
    (comp (ref "R17")
      (value "0")
      (footprint "RES_0402_HIGH")
      (description "SMD Resistor - 0402 (1005 Metric)")
      (fields (field (name "Comment") "RES-0402"))
      (libsource (lib "2256-GaN Power") (part "RES-2"))
    )
    (comp (ref "R18")
      (value "100")
      (footprint "RES_0402_HIGH")
      (description "SMD Resistor - 0402 (1005 Metric)")
      (fields (field (name "Comment") "RES-0402"))
      (libsource (lib "2256-GaN Power") (part "RES-2"))
    )
    (comp (ref "R19")
      (value "10")
      (footprint "RES_0402_HIGH")
      (description "SMD Resistor - 0402 (1005 Metric)")
      (fields (field (name "Comment") "RES-0402"))
      (libsource (lib "2256-GaN Power") (part "RES-2"))
    )
    (comp (ref "R20")
      (value "1k")
      (footprint "RES_1206_MED")
      (description "SMD Resistor - 1206 (3216 Metric)")
      (fields (field (name "Comment") "RES-1206"))
      (libsource (lib "2256-GaN Power") (part "RES-2"))
    )
    (comp (ref "R21")
      (value "100")
      (footprint "RES_0402_HIGH")
      (description "SMD Resistor - 0402 (1005 Metric)")
      (fields (field (name "Comment") "RES-0402"))
      (libsource (lib "2256-GaN Power") (part "RES-2"))
    )
    (comp (ref "R22")
      (value "0.1")
      (footprint "RES_0402_HIGH")
      (description "SMD Resistor - 0402 (1005 Metric)")
      (fields (field (name "Comment") "RES-0402"))
      (libsource (lib "2256-GaN Power") (part "RES-2"))
    )
    (comp (ref "R23")
      (value "0.1")
      (footprint "RES_0402_HIGH")
      (description "SMD Resistor - 0402 (1005 Metric)")
      (fields (field (name "Comment") "RES-0402"))
      (libsource (lib "2256-GaN Power") (part "RES-2"))
    )
    (comp (ref "R24")
      (value "0.1")
      (footprint "RES_0402_HIGH")
      (description "SMD Resistor - 0402 (1005 Metric)")
      (fields (field (name "Comment") "RES-0402"))
      (libsource (lib "2256-GaN Power") (part "RES-2"))
    )
    (comp (ref "R25")
      (value "0.1")
      (footprint "RES_0402_HIGH")
      (description "SMD Resistor - 0402 (1005 Metric)")
      (fields (field (name "Comment") "RES-0402"))
      (libsource (lib "2256-GaN Power") (part "RES-2"))
    )
    (comp (ref "R26")
      (value "0.1")
      (footprint "RES_0402_HIGH")
      (description "SMD Resistor - 0402 (1005 Metric)")
      (fields (field (name "Comment") "RES-0402"))
      (libsource (lib "2256-GaN Power") (part "RES-2"))
    )
    (comp (ref "R27")
      (value "0.1")
      (footprint "RES_0402_HIGH")
      (description "SMD Resistor - 0402 (1005 Metric)")
      (fields (field (name "Comment") "RES-0402"))
      (libsource (lib "2256-GaN Power") (part "RES-2"))
    )
    (comp (ref "R28")
      (value "0.1")
      (footprint "RES_0402_HIGH")
      (description "SMD Resistor - 0402 (1005 Metric)")
      (fields (field (name "Comment") "RES-0402"))
      (libsource (lib "2256-GaN Power") (part "RES-2"))
    )
    (comp (ref "R29")
      (value "0.1")
      (footprint "RES_0402_HIGH")
      (description "SMD Resistor - 0402 (1005 Metric)")
      (fields (field (name "Comment") "RES-0402"))
      (libsource (lib "2256-GaN Power") (part "RES-2"))
    )
    (comp (ref "R30")
      (value "0.1")
      (footprint "RES_0402_HIGH")
      (description "SMD Resistor - 0402 (1005 Metric)")
      (fields (field (name "Comment") "RES-0402"))
      (libsource (lib "2256-GaN Power") (part "RES-2"))
    )
    (comp (ref "R31")
      (value "0.1")
      (footprint "RES_0402_HIGH")
      (description "SMD Resistor - 0402 (1005 Metric)")
      (fields (field (name "Comment") "RES-0402"))
      (libsource (lib "2256-GaN Power") (part "RES-2"))
    )
    (comp (ref "R32")
      (value "680")
      (footprint "RES_0402_HIGH")
      (description "SMD Resistor - 0402 (1005 Metric)")
      (fields (field (name "Comment") "RES-0402"))
      (libsource (lib "2256-GaN Power") (part "RES-2"))
    )
    (comp (ref "R33")
      (value "50")
      (footprint "RES_0402_HIGH")
      (description "SMD Resistor - 0402 (1005 Metric)")
      (fields (field (name "Comment") "RES-0402"))
      (libsource (lib "2256-GaN Power") (part "RES-2"))
    )
    (comp (ref "R34")
      (value "220")
      (footprint "RES_0402_HIGH")
      (description "SMD Resistor - 0402 (1005 Metric)")
      (fields (field (name "Comment") "RES-0402"))
      (libsource (lib "2256-GaN Power") (part "RES-2"))
    )
    (comp (ref "R35")
      (value "50")
      (footprint "RES_0402_HIGH")
      (description "SMD Resistor - 0402 (1005 Metric)")
      (fields (field (name "Comment") "RES-0402"))
      (libsource (lib "2256-GaN Power") (part "RES-2"))
    )
    (comp (ref "R36")
      (value "50")
      (footprint "RES_0402_HIGH")
      (description "SMD Resistor - 0402 (1005 Metric)")
      (fields (field (name "Comment") "RES-0402"))
      (libsource (lib "2256-GaN Power") (part "RES-2"))
    )
    (comp (ref "R37")
      (value "220")
      (footprint "RES_0402_HIGH")
      (description "SMD Resistor - 0402 (1005 Metric)")
      (fields (field (name "Comment") "RES-0402"))
      (libsource (lib "2256-GaN Power") (part "RES-2"))
    )
    (comp (ref "R38")
      (value "50")
      (footprint "RES_0402_HIGH")
      (description "SMD Resistor - 0402 (1005 Metric)")
      (fields (field (name "Comment") "RES-0402"))
      (libsource (lib "2256-GaN Power") (part "RES-2"))
    )
    (comp (ref "R39")
      (value "50")
      (footprint "RES_0402_HIGH")
      (description "SMD Resistor - 0402 (1005 Metric)")
      (fields (field (name "Comment") "RES-0402"))
      (libsource (lib "2256-GaN Power") (part "RES-2"))
    )
    (comp (ref "R40")
      (value "680")
      (footprint "RES_0402_HIGH")
      (description "SMD Resistor - 0402 (1005 Metric)")
      (fields (field (name "Comment") "RES-0402"))
      (libsource (lib "2256-GaN Power") (part "RES-2"))
    )
    (comp (ref "R49")
      (value "0.1")
      (footprint "RES_0402_HIGH")
      (description "SMD Resistor - 0402 (1005 Metric)")
      (fields (field (name "Comment") "RES-0402"))
      (libsource (lib "2256-GaN Power") (part "RES-2"))
    )
    (comp (ref "R50")
      (value "0.1")
      (footprint "RES_0402_HIGH")
      (description "SMD Resistor - 0402 (1005 Metric)")
      (fields (field (name "Comment") "RES-0402"))
      (libsource (lib "2256-GaN Power") (part "RES-2"))
    )
    (comp (ref "R51")
      (value "0.1")
      (footprint "RES_0402_HIGH")
      (description "SMD Resistor - 0402 (1005 Metric)")
      (fields (field (name "Comment") "RES-0402"))
      (libsource (lib "2256-GaN Power") (part "RES-2"))
    )
    (comp (ref "R52")
      (value "0.1")
      (footprint "RES_0402_HIGH")
      (description "SMD Resistor - 0402 (1005 Metric)")
      (fields (field (name "Comment") "RES-0402"))
      (libsource (lib "2256-GaN Power") (part "RES-2"))
    )
    (comp (ref "R53")
      (value "0.1")
      (footprint "RES_0402_HIGH")
      (description "SMD Resistor - 0402 (1005 Metric)")
      (fields (field (name "Comment") "RES-0402"))
      (libsource (lib "2256-GaN Power") (part "RES-2"))
    )
    (comp (ref "R54")
      (value "0.1")
      (footprint "RES_0402_HIGH")
      (description "SMD Resistor - 0402 (1005 Metric)")
      (fields (field (name "Comment") "RES-0402"))
      (libsource (lib "2256-GaN Power") (part "RES-2"))
    )
    (comp (ref "R55")
      (value "0.1")
      (footprint "RES_0402_HIGH")
      (description "SMD Resistor - 0402 (1005 Metric)")
      (fields (field (name "Comment") "RES-0402"))
      (libsource (lib "2256-GaN Power") (part "RES-2"))
    )
    (comp (ref "R56")
      (value "0.1")
      (footprint "RES_0402_HIGH")
      (description "SMD Resistor - 0402 (1005 Metric)")
      (fields (field (name "Comment") "RES-0402"))
      (libsource (lib "2256-GaN Power") (part "RES-2"))
    )
    (comp (ref "R57")
      (value "0.1")
      (footprint "RES_0402_HIGH")
      (description "SMD Resistor - 0402 (1005 Metric)")
      (fields (field (name "Comment") "RES-0402"))
      (libsource (lib "2256-GaN Power") (part "RES-2"))
    )
    (comp (ref "R58")
      (value "0.1")
      (footprint "RES_0402_HIGH")
      (description "SMD Resistor - 0402 (1005 Metric)")
      (fields (field (name "Comment") "RES-0402"))
      (libsource (lib "2256-GaN Power") (part "RES-2"))
    )
    (comp (ref "RSET1")
      (value "1k")
      (footprint "RES_0603_MED")
      (description "SMD Resistor - 0603 (1608 Metric)")
      (fields (field (name "Comment") "RES-0603"))
      (libsource (lib "2256-GaN Power") (part "RES-2"))
    )
    (comp (ref "RSET2")
      (value "1k")
      (footprint "RES_0603_MED")
      (description "SMD Resistor - 0603 (1608 Metric)")
      (fields (field (name "Comment") "RES-0603"))
      (libsource (lib "2256-GaN Power") (part "RES-2"))
    )
    (comp (ref "RSET3")
      (value "1k")
      (footprint "RES_0603_MED")
      (description "SMD Resistor - 0603 (1608 Metric)")
      (fields (field (name "Comment") "RES-0603"))
      (libsource (lib "2256-GaN Power") (part "RES-2"))
    )
    (comp (ref "RSET4")
      (value "1k")
      (footprint "RES_0603_MED")
      (description "SMD Resistor - 0603 (1608 Metric)")
      (fields (field (name "Comment") "RES-0603"))
      (libsource (lib "2256-GaN Power") (part "RES-2"))
    )
    (comp (ref "Sig V+1")
      (value "Testpoint")
      (footprint "Testpoint-Footprint-1")
      (description "testpoint for circuit")
      (libsource (lib "2256-GaN Power") (part "Testpoint-Symbol-1"))
    )
    (comp (ref "SigGND1")
      (value "Testpoint")
      (footprint "Testpoint-Footprint-1")
      (description "testpoint for circuit")
      (libsource (lib "2256-GaN Power") (part "Testpoint-Symbol-1"))
    )
    (comp (ref "SigGND2")
      (value "Testpoint")
      (footprint "Testpoint-Footprint-1")
      (description "testpoint for circuit")
      (libsource (lib "2256-GaN Power") (part "Testpoint-Symbol-1"))
    )
    (comp (ref "SigGND3")
      (value "Testpoint")
      (footprint "Testpoint-Footprint-1")
      (description "testpoint for circuit")
      (libsource (lib "2256-GaN Power") (part "Testpoint-Symbol-1"))
    )
    (comp (ref "SigGND4")
      (value "Testpoint")
      (footprint "Testpoint-Footprint-1")
      (description "testpoint for circuit")
      (libsource (lib "2256-GaN Power") (part "Testpoint-Symbol-1"))
    )
    (comp (ref "Source1")
      (value "Testpoint")
      (footprint "Testpoint-Footprint-1")
      (description "testpoint for circuit")
      (libsource (lib "2256-GaN Power") (part "Testpoint-Symbol-1"))
    )
    (comp (ref "U1")
      (value "AZ1117H-ADJTRE1")
      (footprint "SOT-223")
      (description "IC REG LINEAR POS ADJ 1A SOT223")
      (libsource (lib "2256-GaN Power") (part "AZ1117H-ADJTRE1"))
    )
    (comp (ref "U2")
      (value "AZ1117H-ADJTRE1")
      (footprint "SOT-223")
      (description "IC REG LINEAR POS ADJ 1A SOT223")
      (libsource (lib "2256-GaN Power") (part "AZ1117H-ADJTRE1"))
    )
    (comp (ref "U3")
      (value "MAX1735EUK50+T")
      (footprint "FP-U5-2-IPC_B")
      (description "IC REG LIN NEG ADJ 200MA SOT23-5")
      (libsource (lib "Altium Content Vault") (part "3fe5ddc4f403acdf696fd8e1856eecf"))
    )
    (comp (ref "U4")
      (value "MAX1735EUK50+T")
      (footprint "FP-U5-2-IPC_B")
      (description "IC REG LIN NEG ADJ 200MA SOT23-5")
      (libsource (lib "Altium Content Vault") (part "3fe5ddc4f403acdf696fd8e1856eecf"))
    )
    (comp (ref "U5")
      (value "AZ1117IH-5.0TRG1")
      (footprint "SOT230P700X180-4N")
      (description "https://www.digikey.ca/en/products/detail/diodes-incorporated/AZ1117IH-5-0TRG1/5699673")
      (libsource (lib "2256-GaN Power") (part "AZ1117IH-5.0TRG1-Symbol-1"))
    )
    (comp (ref "U6")
      (value "THS4508RGTT")
      (footprint "QFN-16")
      (description "WIDEBAND, LOW NOISE, LOW DISTORTION FULLY DIFFERENTIAL AMPLIFIER")
      (libsource (lib "2256-GaN Power") (part "THS4508"))
    )
    (comp (ref "Vdd1")
      (value "Testpoint")
      (footprint "Testpoint-Footprint-1")
      (description "testpoint for circuit")
      (libsource (lib "2256-GaN Power") (part "Testpoint-Symbol-1"))
    )
    (comp (ref "VR1")
      (value "500")
      (footprint "TRIM_J-LEAD")
      (description "Potentiometer, J-Lead Trim Pot")
      (fields (field (name "Comment") "RES_POT_JLEAD"))
      (libsource (lib "2256-GaN Power") (part "RES-POT-3"))
    )
    (comp (ref "VR2")
      (value "500")
      (footprint "TRIM_J-LEAD")
      (description "Potentiometer, J-Lead Trim Pot")
      (fields (field (name "Comment") "RES_POT_JLEAD"))
      (libsource (lib "2256-GaN Power") (part "RES-POT-3"))
    )
    (comp (ref "VR3")
      (value "5k")
      (footprint "TRIM_J-LEAD")
      (description "Potentiometer, J-Lead Trim Pot")
      (fields (field (name "Comment") "RES_POT_JLEAD"))
      (libsource (lib "2256-GaN Power") (part "RES-POT-3"))
    )
    (comp (ref "VR4")
      (value "5k")
      (footprint "TRIM_J-LEAD")
      (description "Potentiometer, J-Lead Trim Pot")
      (fields (field (name "Comment") "RES_POT_JLEAD"))
      (libsource (lib "2256-GaN Power") (part "RES-POT-3"))
    )
  )
  (nets
    (net (code "1") (name "+5") (class "Default")
      (node (ref "+5 V") (pin "1") (pinfunction "1_1") (pintype "passive"))
      (node (ref "C5") (pin "2") (pinfunction "2_2") (pintype "passive"))
      (node (ref "C51") (pin "2") (pinfunction "2_2") (pintype "passive"))
      (node (ref "C52") (pin "2") (pinfunction "2_2") (pintype "passive"))
      (node (ref "C55") (pin "2") (pinfunction "2_2") (pintype "passive"))
      (node (ref "C56") (pin "2") (pinfunction "2_2") (pintype "passive"))
      (node (ref "C57") (pin "2") (pinfunction "2_2") (pintype "passive"))
      (node (ref "C8") (pin "2") (pinfunction "2_2") (pintype "passive"))
      (node (ref "U5") (pin "2") (pinfunction "OUT_(5V)_2") (pintype "passive"))
      (node (ref "U5") (pin "4") (pinfunction "OUT_4") (pintype "passive"))
      (node (ref "U6") (pin "12") (pinfunction "~{PD}_12") (pintype "passive"))
      (node (ref "U6") (pin "5") (pinfunction "VS+_5") (pintype "power_in"))
      (node (ref "U6") (pin "6") (pinfunction "VS+_6") (pintype "power_in"))
      (node (ref "U6") (pin "7") (pinfunction "VS+_7") (pintype "power_in"))
      (node (ref "U6") (pin "8") (pinfunction "VS+_8") (pintype "power_in"))
    )
    (net (code "2") (name "+5_SIG") (class "Default")
      (node (ref "C29") (pin "1") (pinfunction "1_1") (pintype "passive"))
      (node (ref "C30") (pin "1") (pinfunction "1_1") (pintype "passive"))
      (node (ref "J5") (pin "1") (pinfunction "1_1") (pintype "passive"))
      (node (ref "R14") (pin "2") (pinfunction "2_2") (pintype "passive"))
      (node (ref "R18") (pin "2") (pinfunction "2_2") (pintype "passive"))
      (node (ref "R3") (pin "2") (pinfunction "2_2") (pintype "passive"))
      (node (ref "R6") (pin "2") (pinfunction "2_2") (pintype "passive"))
      (node (ref "Sig V+1") (pin "1") (pinfunction "1_1") (pintype "passive"))
    )
    (net (code "3") (name "+VIN") (class "Default")
      (node (ref "C46") (pin "1") (pinfunction "1_1") (pintype "passive"))
      (node (ref "C47") (pin "1") (pinfunction "1_1") (pintype "passive"))
      (node (ref "C48") (pin "1") (pinfunction "1_1") (pintype "passive"))
      (node (ref "C49") (pin "2") (pinfunction "2_2") (pintype "passive"))
      (node (ref "C50") (pin "2") (pinfunction "2_2") (pintype "passive"))
      (node (ref "J11") (pin "1") (pinfunction "1_1") (pintype "passive"))
      (node (ref "U5") (pin "3") (pinfunction "IN_3") (pintype "passive"))
    )
    (net (code "6") (name "/GATE_OUT") (class "Default")
      (node (ref "G1") (pin "3") (pinfunction "G_3") (pintype "passive"))
      (node (ref "H_Gate1") (pin "1") (pinfunction "1_1") (pintype "passive"))
      (node (ref "R7") (pin "2") (pinfunction "2_2") (pintype "passive"))
    )
    (net (code "7") (name "/L_Gate") (class "Default")
      (node (ref "G2") (pin "3") (pinfunction "G_3") (pintype "passive"))
      (node (ref "L_Gate1") (pin "1") (pinfunction "1_1") (pintype "passive"))
      (node (ref "R19") (pin "2") (pinfunction "2_2") (pintype "passive"))
    )
    (net (code "8") (name "/SIG_V+") (class "Default")
      (node (ref "LSig1") (pin "1") (pinfunction "1_1") (pintype "passive"))
      (node (ref "R13") (pin "2") (pinfunction "2_2") (pintype "passive"))
      (node (ref "R14") (pin "1") (pinfunction "1_1") (pintype "passive"))
      (node (ref "R16") (pin "2") (pinfunction "2_2") (pintype "passive"))
    )
    (net (code "9") (name "/SIG_V+_1") (class "Default")
      (node (ref "HSig1") (pin "1") (pinfunction "1_1") (pintype "passive"))
      (node (ref "R2") (pin "2") (pinfunction "2_2") (pintype "passive"))
      (node (ref "R3") (pin "1") (pinfunction "1_1") (pintype "passive"))
      (node (ref "R4") (pin "2") (pinfunction "2_2") (pintype "passive"))
    )
    (net (code "10") (name "/SIG_V-") (class "Default")
      (node (ref "R17") (pin "2") (pinfunction "2_2") (pintype "passive"))
      (node (ref "R18") (pin "1") (pinfunction "1_1") (pintype "passive"))
      (node (ref "R21") (pin "2") (pinfunction "2_2") (pintype "passive"))
      (node (ref "nLSig1") (pin "1") (pinfunction "1_1") (pintype "passive"))
    )
    (net (code "11") (name "/SIG_V-_1") (class "Default")
      (node (ref "R10") (pin "2") (pinfunction "2_2") (pintype "passive"))
      (node (ref "R5") (pin "2") (pinfunction "2_2") (pintype "passive"))
      (node (ref "R6") (pin "1") (pinfunction "1_1") (pintype "passive"))
      (node (ref "nHSig1") (pin "1") (pinfunction "1_1") (pintype "passive"))
    )
    (net (code "12") (name "/SW_NODE") (class "Default")
      (node (ref "C39") (pin "1") (pinfunction "1_1") (pintype "passive"))
      (node (ref "G1") (pin "1") (pinfunction "S_1") (pintype "passive"))
      (node (ref "G2") (pin "4") (pinfunction "D_4") (pintype "passive"))
      (node (ref "J6") (pin "1") (pinfunction "1_1") (pintype "passive"))
    )
    (net (code "13") (name "/Source") (class "Default")
      (node (ref "G2") (pin "1") (pinfunction "S_1") (pintype "passive"))
      (node (ref "J14") (pin "1") (pinfunction "1_1") (pintype "passive"))
      (node (ref "R22") (pin "2") (pinfunction "2_2") (pintype "passive"))
      (node (ref "R23") (pin "2") (pinfunction "2_2") (pintype "passive"))
      (node (ref "R24") (pin "2") (pinfunction "2_2") (pintype "passive"))
      (node (ref "R25") (pin "2") (pinfunction "2_2") (pintype "passive"))
      (node (ref "R26") (pin "2") (pinfunction "2_2") (pintype "passive"))
      (node (ref "R27") (pin "2") (pinfunction "2_2") (pintype "passive"))
      (node (ref "R28") (pin "2") (pinfunction "2_2") (pintype "passive"))
      (node (ref "R29") (pin "2") (pinfunction "2_2") (pintype "passive"))
      (node (ref "R30") (pin "2") (pinfunction "2_2") (pintype "passive"))
      (node (ref "R31") (pin "2") (pinfunction "2_2") (pintype "passive"))
      (node (ref "R34") (pin "2") (pinfunction "2_2") (pintype "passive"))
      (node (ref "R49") (pin "2") (pinfunction "2_2") (pintype "passive"))
      (node (ref "R50") (pin "2") (pinfunction "2_2") (pintype "passive"))
      (node (ref "R51") (pin "2") (pinfunction "2_2") (pintype "passive"))
      (node (ref "R52") (pin "2") (pinfunction "2_2") (pintype "passive"))
      (node (ref "R53") (pin "2") (pinfunction "2_2") (pintype "passive"))
      (node (ref "R54") (pin "2") (pinfunction "2_2") (pintype "passive"))
      (node (ref "R55") (pin "2") (pinfunction "2_2") (pintype "passive"))
      (node (ref "R56") (pin "2") (pinfunction "2_2") (pintype "passive"))
      (node (ref "R57") (pin "2") (pinfunction "2_2") (pintype "passive"))
      (node (ref "R58") (pin "2") (pinfunction "2_2") (pintype "passive"))
      (node (ref "Source1") (pin "1") (pinfunction "1_1") (pintype "passive"))
    )
    (net (code "14") (name "GND_SIG") (class "Default")
      (node (ref "C29") (pin "2") (pinfunction "2_2") (pintype "passive"))
      (node (ref "C30") (pin "2") (pinfunction "2_2") (pintype "passive"))
      (node (ref "J7") (pin "1") (pinfunction "1_1") (pintype "passive"))
      (node (ref "R10") (pin "1") (pinfunction "1_1") (pintype "passive"))
      (node (ref "R13") (pin "1") (pinfunction "1_1") (pintype "passive"))
      (node (ref "R2") (pin "1") (pinfunction "1_1") (pintype "passive"))
      (node (ref "R21") (pin "1") (pinfunction "1_1") (pintype "passive"))
      (node (ref "SigGND1") (pin "1") (pinfunction "1_1") (pintype "passive"))
      (node (ref "SigGND2") (pin "1") (pinfunction "1_1") (pintype "passive"))
      (node (ref "SigGND3") (pin "1") (pinfunction "1_1") (pintype "passive"))
      (node (ref "SigGND4") (pin "1") (pinfunction "1_1") (pintype "passive"))
    )
    (net (code "15") (name "H_+V") (class "Default")
      (node (ref "C17") (pin "1") (pinfunction "1_1") (pintype "passive"))
      (node (ref "C18") (pin "1") (pinfunction "1_1") (pintype "passive"))
      (node (ref "C40") (pin "1") (pinfunction "1_1") (pintype "passive"))
      (node (ref "C41") (pin "1") (pinfunction "1_1") (pintype "passive"))
      (node (ref "H +V1") (pin "1") (pinfunction "1_1") (pintype "passive"))
      (node (ref "U2") (pin "2") (pinfunction "VOUT_2") (pintype "passive"))
      (node (ref "U2") (pin "4") (pinfunction "VOUT_4") (pintype "passive"))
      (node (ref "VR2") (pin "1") (pinfunction "CCW_1") (pintype "passive"))
    )
    (net (code "16") (name "H_+VIN") (class "Default")
      (node (ref "C15") (pin "1") (pinfunction "1_1") (pintype "passive"))
      (node (ref "C16") (pin "1") (pinfunction "1_1") (pintype "passive"))
      (node (ref "C45") (pin "1") (pinfunction "1_1") (pintype "passive"))
      (node (ref "J9") (pin "1") (pinfunction "1_1") (pintype "passive"))
      (node (ref "U2") (pin "3") (pinfunction "VIN_3") (pintype "passive"))
    )
    (net (code "17") (name "H_-V") (class "Default")
      (node (ref "C27") (pin "1") (pinfunction "1_1") (pintype "passive"))
      (node (ref "C28") (pin "1") (pinfunction "1_1") (pintype "passive"))
      (node (ref "C42") (pin "1") (pinfunction "1_1") (pintype "passive"))
      (node (ref "C43") (pin "1") (pinfunction "1_1") (pintype "passive"))
      (node (ref "H -V1") (pin "1") (pinfunction "1_1") (pintype "passive"))
      (node (ref "U4") (pin "5") (pinfunction "OUT_5") (pintype "passive"))
      (node (ref "VR4") (pin "2") (pinfunction "S_2") (pintype "passive"))
      (node (ref "VR4") (pin "3") (pinfunction "CW_3") (pintype "passive"))
    )
    (net (code "18") (name "H_-VIN") (class "Default")
      (node (ref "C25") (pin "1") (pinfunction "1_1") (pintype "passive"))
      (node (ref "C26") (pin "1") (pinfunction "1_1") (pintype "passive"))
      (node (ref "C54") (pin "2") (pinfunction "2_2") (pintype "passive"))
      (node (ref "J19") (pin "1") (pinfunction "1_1") (pintype "passive"))
      (node (ref "R9") (pin "1") (pinfunction "1_1") (pintype "passive"))
      (node (ref "U4") (pin "2") (pinfunction "IN_2") (pintype "power_in"))
    )
    (net (code "19") (name "H_SS") (class "Default")
      (node (ref "C15") (pin "2") (pinfunction "2_2") (pintype "passive"))
      (node (ref "C16") (pin "2") (pinfunction "2_2") (pintype "passive"))
      (node (ref "C17") (pin "2") (pinfunction "2_2") (pintype "passive"))
      (node (ref "C18") (pin "2") (pinfunction "2_2") (pintype "passive"))
      (node (ref "C20") (pin "1") (pinfunction "1_1") (pintype "passive"))
      (node (ref "C25") (pin "2") (pinfunction "2_2") (pintype "passive"))
      (node (ref "C26") (pin "2") (pinfunction "2_2") (pintype "passive"))
      (node (ref "C27") (pin "2") (pinfunction "2_2") (pintype "passive"))
      (node (ref "C28") (pin "2") (pinfunction "2_2") (pintype "passive"))
      (node (ref "C37") (pin "1") (pinfunction "1_1") (pintype "passive"))
      (node (ref "C38") (pin "1") (pinfunction "1_1") (pintype "passive"))
      (node (ref "C40") (pin "2") (pinfunction "2_2") (pintype "passive"))
      (node (ref "C41") (pin "2") (pinfunction "2_2") (pintype "passive"))
      (node (ref "C42") (pin "2") (pinfunction "2_2") (pintype "passive"))
      (node (ref "C43") (pin "2") (pinfunction "2_2") (pintype "passive"))
      (node (ref "C45") (pin "2") (pinfunction "2_2") (pintype "passive"))
      (node (ref "C54") (pin "1") (pinfunction "1_1") (pintype "passive"))
      (node (ref "G1") (pin "2") (pinfunction "KS_2") (pintype "passive"))
      (node (ref "H_SS1") (pin "1") (pinfunction "1_1") (pintype "passive"))
      (node (ref "H_SS2") (pin "1") (pinfunction "1_1") (pintype "passive"))
      (node (ref "H_SS3") (pin "1") (pinfunction "1_1") (pintype "passive"))
      (node (ref "J13") (pin "1") (pinfunction "1_1") (pintype "passive"))
      (node (ref "J17") (pin "1") (pinfunction "1_1") (pintype "passive"))
      (node (ref "R12") (pin "2") (pinfunction "2_2") (pintype "passive"))
      (node (ref "R7") (pin "1") (pinfunction "1_1") (pintype "passive"))
      (node (ref "RSET2") (pin "1") (pinfunction "1_1") (pintype "passive"))
      (node (ref "RSET4") (pin "1") (pinfunction "1_1") (pintype "passive"))
      (node (ref "U4") (pin "1") (pinfunction "GND_1") (pintype "power_in"))
    )
    (net (code "20") (name "L_+V") (class "Default")
      (node (ref "C13") (pin "1") (pinfunction "1_1") (pintype "passive"))
      (node (ref "C14") (pin "1") (pinfunction "1_1") (pintype "passive"))
      (node (ref "C31") (pin "1") (pinfunction "1_1") (pintype "passive"))
      (node (ref "C32") (pin "1") (pinfunction "1_1") (pintype "passive"))
      (node (ref "L +V1") (pin "1") (pinfunction "1_1") (pintype "passive"))
      (node (ref "U1") (pin "2") (pinfunction "VOUT_2") (pintype "passive"))
      (node (ref "U1") (pin "4") (pinfunction "VOUT_4") (pintype "passive"))
      (node (ref "VR1") (pin "1") (pinfunction "CCW_1") (pintype "passive"))
    )
    (net (code "21") (name "L_+VIN") (class "Default")
      (node (ref "C11") (pin "1") (pinfunction "1_1") (pintype "passive"))
      (node (ref "C12") (pin "1") (pinfunction "1_1") (pintype "passive"))
      (node (ref "C44") (pin "1") (pinfunction "1_1") (pintype "passive"))
      (node (ref "J8") (pin "1") (pinfunction "1_1") (pintype "passive"))
      (node (ref "U1") (pin "3") (pinfunction "VIN_3") (pintype "passive"))
    )
    (net (code "22") (name "L_-V") (class "Default")
      (node (ref "C23") (pin "1") (pinfunction "1_1") (pintype "passive"))
      (node (ref "C24") (pin "1") (pinfunction "1_1") (pintype "passive"))
      (node (ref "C33") (pin "1") (pinfunction "1_1") (pintype "passive"))
      (node (ref "C34") (pin "1") (pinfunction "1_1") (pintype "passive"))
      (node (ref "L -V1") (pin "1") (pinfunction "1_1") (pintype "passive"))
      (node (ref "U3") (pin "5") (pinfunction "OUT_5") (pintype "passive"))
      (node (ref "VR3") (pin "2") (pinfunction "S_2") (pintype "passive"))
      (node (ref "VR3") (pin "3") (pinfunction "CW_3") (pintype "passive"))
    )
    (net (code "23") (name "L_-VIN") (class "Default")
      (node (ref "C21") (pin "1") (pinfunction "1_1") (pintype "passive"))
      (node (ref "C22") (pin "1") (pinfunction "1_1") (pintype "passive"))
      (node (ref "C53") (pin "2") (pinfunction "2_2") (pintype "passive"))
      (node (ref "J18") (pin "1") (pinfunction "1_1") (pintype "passive"))
      (node (ref "R8") (pin "1") (pinfunction "1_1") (pintype "passive"))
      (node (ref "U3") (pin "2") (pinfunction "IN_2") (pintype "power_in"))
    )
    (net (code "24") (name "L_SS") (class "Default")
      (node (ref "C11") (pin "2") (pinfunction "2_2") (pintype "passive"))
      (node (ref "C12") (pin "2") (pinfunction "2_2") (pintype "passive"))
      (node (ref "C13") (pin "2") (pinfunction "2_2") (pintype "passive"))
      (node (ref "C14") (pin "2") (pinfunction "2_2") (pintype "passive"))
      (node (ref "C19") (pin "1") (pinfunction "1_1") (pintype "passive"))
      (node (ref "C21") (pin "2") (pinfunction "2_2") (pintype "passive"))
      (node (ref "C22") (pin "2") (pinfunction "2_2") (pintype "passive"))
      (node (ref "C23") (pin "2") (pinfunction "2_2") (pintype "passive"))
      (node (ref "C24") (pin "2") (pinfunction "2_2") (pintype "passive"))
      (node (ref "C31") (pin "2") (pinfunction "2_2") (pintype "passive"))
      (node (ref "C32") (pin "2") (pinfunction "2_2") (pintype "passive"))
      (node (ref "C33") (pin "2") (pinfunction "2_2") (pintype "passive"))
      (node (ref "C34") (pin "2") (pinfunction "2_2") (pintype "passive"))
      (node (ref "C35") (pin "1") (pinfunction "1_1") (pintype "passive"))
      (node (ref "C36") (pin "1") (pinfunction "1_1") (pintype "passive"))
      (node (ref "C44") (pin "2") (pinfunction "2_2") (pintype "passive"))
      (node (ref "C53") (pin "1") (pinfunction "1_1") (pintype "passive"))
      (node (ref "G2") (pin "2") (pinfunction "KS_2") (pintype "passive"))
      (node (ref "J12") (pin "1") (pinfunction "1_1") (pintype "passive"))
      (node (ref "J16") (pin "1") (pinfunction "1_1") (pintype "passive"))
      (node (ref "L_SS1") (pin "1") (pinfunction "1_1") (pintype "passive"))
      (node (ref "L_SS2") (pin "1") (pinfunction "1_1") (pintype "passive"))
      (node (ref "L_SS3") (pin "1") (pinfunction "1_1") (pintype "passive"))
      (node (ref "R11") (pin "2") (pinfunction "2_2") (pintype "passive"))
      (node (ref "R19") (pin "1") (pinfunction "1_1") (pintype "passive"))
      (node (ref "RSET1") (pin "1") (pinfunction "1_1") (pintype "passive"))
      (node (ref "RSET3") (pin "1") (pinfunction "1_1") (pintype "passive"))
      (node (ref "U3") (pin "1") (pinfunction "GND_1") (pintype "power_in"))
    )
    (net (code "25") (name "Net-(C39-Pad2)") (class "Default")
      (node (ref "C39") (pin "2") (pinfunction "2_2") (pintype "passive"))
      (node (ref "R15") (pin "2") (pinfunction "2_2") (pintype "passive"))
    )
    (net (code "26") (name "Net-(C58-Pad2)") (class "Default")
      (node (ref "C58") (pin "2") (pinfunction "2_2") (pintype "passive"))
      (node (ref "U6") (pin "9") (pinfunction "CM_9") (pintype "passive"))
    )
    (net (code "27") (name "Net-(C59-Pad2)") (class "Default")
      (node (ref "C59") (pin "2") (pinfunction "2_2") (pintype "passive"))
      (node (ref "C60") (pin "1") (pinfunction "1_1") (pintype "passive"))
      (node (ref "J21") (pin "1") (pinfunction "1_1") (pintype "passive"))
      (node (ref "R33") (pin "2") (pinfunction "2_2") (pintype "passive"))
      (node (ref "R35") (pin "1") (pinfunction "1_1") (pintype "passive"))
      (node (ref "R36") (pin "2") (pinfunction "2_2") (pintype "passive"))
    )
    (net (code "28") (name "Net-(C60-Pad2)") (class "Default")
      (node (ref "C60") (pin "2") (pinfunction "2_2") (pintype "passive"))
      (node (ref "C61") (pin "1") (pinfunction "1_1") (pintype "passive"))
      (node (ref "J22") (pin "1") (pinfunction "1_1") (pintype "passive"))
      (node (ref "R36") (pin "1") (pinfunction "1_1") (pintype "passive"))
      (node (ref "R38") (pin "1") (pinfunction "1_1") (pintype "passive"))
      (node (ref "R39") (pin "2") (pinfunction "2_2") (pintype "passive"))
    )
    (net (code "29") (name "Net-(C62-Pad2)") (class "Default")
      (node (ref "C62") (pin "2") (pinfunction "2_2") (pintype "passive"))
      (node (ref "U6") (pin "4") (pinfunction "CM_4") (pintype "passive"))
    )
    (net (code "30") (name "Net-(J4-Pad1)") (class "Default")
      (node (ref "J4") (pin "1") (pinfunction "1_1") (pintype "passive"))
      (node (ref "R4") (pin "1") (pinfunction "1_1") (pintype "passive"))
    )
    (net (code "31") (name "Net-(J4-Pad2)") (class "Default")
      (node (ref "J4") (pin "2") (pinfunction "2_2") (pintype "passive"))
      (node (ref "R5") (pin "1") (pinfunction "1_1") (pintype "passive"))
    )
    (net (code "32") (name "Net-(J10-Pad1)") (class "Default")
      (node (ref "J10") (pin "1") (pinfunction "1_1") (pintype "passive"))
      (node (ref "R16") (pin "1") (pinfunction "1_1") (pintype "passive"))
    )
    (net (code "33") (name "Net-(J10-Pad2)") (class "Default")
      (node (ref "J10") (pin "2") (pinfunction "2_2") (pintype "passive"))
      (node (ref "R17") (pin "1") (pinfunction "1_1") (pintype "passive"))
    )
    (net (code "34") (name "Net-(R15-Pad1)") (class "Default")
      (node (ref "R15") (pin "1") (pinfunction "1_1") (pintype "passive"))
      (node (ref "R20") (pin "2") (pinfunction "2_2") (pintype "passive"))
    )
    (net (code "35") (name "Net-(U1-ADJ{slash}GND)") (class "Default")
      (node (ref "C19") (pin "2") (pinfunction "2_2") (pintype "passive"))
      (node (ref "RSET1") (pin "2") (pinfunction "2_2") (pintype "passive"))
      (node (ref "U1") (pin "1") (pinfunction "ADJ/GND_1") (pintype "passive"))
      (node (ref "VR1") (pin "2") (pinfunction "S_2") (pintype "passive"))
      (node (ref "VR1") (pin "3") (pinfunction "CW_3") (pintype "passive"))
    )
    (net (code "36") (name "Net-(U2-ADJ{slash}GND)") (class "Default")
      (node (ref "C20") (pin "2") (pinfunction "2_2") (pintype "passive"))
      (node (ref "RSET2") (pin "2") (pinfunction "2_2") (pintype "passive"))
      (node (ref "U2") (pin "1") (pinfunction "ADJ/GND_1") (pintype "passive"))
      (node (ref "VR2") (pin "2") (pinfunction "S_2") (pintype "passive"))
      (node (ref "VR2") (pin "3") (pinfunction "CW_3") (pintype "passive"))
    )
    (net (code "37") (name "Net-(U3-SET)") (class "Default")
      (node (ref "C36") (pin "2") (pinfunction "2_2") (pintype "passive"))
      (node (ref "RSET3") (pin "2") (pinfunction "2_2") (pintype "passive"))
      (node (ref "U3") (pin "4") (pinfunction "SET_4") (pintype "input"))
      (node (ref "VR3") (pin "1") (pinfunction "CCW_1") (pintype "passive"))
    )
    (net (code "38") (name "Net-(U3-~{SHDN})") (class "Default")
      (node (ref "C35") (pin "2") (pinfunction "2_2") (pintype "passive"))
      (node (ref "R11") (pin "1") (pinfunction "1_1") (pintype "passive"))
      (node (ref "R8") (pin "2") (pinfunction "2_2") (pintype "passive"))
      (node (ref "U3") (pin "3") (pinfunction "~{SHDN}_3") (pintype "input"))
    )
    (net (code "39") (name "Net-(U4-SET)") (class "Default")
      (node (ref "C38") (pin "2") (pinfunction "2_2") (pintype "passive"))
      (node (ref "RSET4") (pin "2") (pinfunction "2_2") (pintype "passive"))
      (node (ref "U4") (pin "4") (pinfunction "SET_4") (pintype "input"))
      (node (ref "VR4") (pin "1") (pinfunction "CCW_1") (pintype "passive"))
    )
    (net (code "40") (name "Net-(U4-~{SHDN})") (class "Default")
      (node (ref "C37") (pin "2") (pinfunction "2_2") (pintype "passive"))
      (node (ref "R12") (pin "1") (pinfunction "1_1") (pintype "passive"))
      (node (ref "R9") (pin "2") (pinfunction "2_2") (pintype "passive"))
      (node (ref "U4") (pin "3") (pinfunction "~{SHDN}_3") (pintype "input"))
    )
    (net (code "41") (name "Net-(U6-VIN+)") (class "Default")
      (node (ref "R37") (pin "1") (pinfunction "1_1") (pintype "passive"))
      (node (ref "R40") (pin "2") (pinfunction "2_2") (pintype "passive"))
      (node (ref "U6") (pin "11") (pinfunction "VIN+_11") (pintype "passive"))
    )
    (net (code "42") (name "Net-(U6-VIN-)") (class "Default")
      (node (ref "R32") (pin "2") (pinfunction "2_2") (pintype "passive"))
      (node (ref "R34") (pin "1") (pinfunction "1_1") (pintype "passive"))
      (node (ref "U6") (pin "2") (pinfunction "VIN-_2") (pintype "passive"))
    )
    (net (code "43") (name "Net-(U6-VOUT+)") (class "Default")
      (node (ref "R32") (pin "1") (pinfunction "1_1") (pintype "passive"))
      (node (ref "R35") (pin "2") (pinfunction "2_2") (pintype "passive"))
      (node (ref "U6") (pin "3") (pinfunction "VOUT+_3") (pintype "output"))
    )
    (net (code "44") (name "Net-(U6-VOUT-)") (class "Default")
      (node (ref "R38") (pin "2") (pinfunction "2_2") (pintype "passive"))
      (node (ref "R40") (pin "1") (pinfunction "1_1") (pintype "passive"))
      (node (ref "U6") (pin "10") (pinfunction "VOUT-_10") (pintype "output"))
    )
    (net (code "45") (name "PGND") (class "Default")
      (node (ref "C1") (pin "2") (pinfunction "2_2") (pintype "passive"))
      (node (ref "C2") (pin "2") (pinfunction "2_2") (pintype "passive"))
      (node (ref "C3") (pin "2") (pinfunction "2_2") (pintype "passive"))
      (node (ref "C4") (pin "2") (pinfunction "2_2") (pintype "passive"))
      (node (ref "C46") (pin "2") (pinfunction "2_2") (pintype "passive"))
      (node (ref "C47") (pin "2") (pinfunction "2_2") (pintype "passive"))
      (node (ref "C48") (pin "2") (pinfunction "2_2") (pintype "passive"))
      (node (ref "C49") (pin "1") (pinfunction "1_1") (pintype "passive"))
      (node (ref "C5") (pin "1") (pinfunction "1_1") (pintype "passive"))
      (node (ref "C50") (pin "1") (pinfunction "1_1") (pintype "passive"))
      (node (ref "C51") (pin "1") (pinfunction "1_1") (pintype "passive"))
      (node (ref "C52") (pin "1") (pinfunction "1_1") (pintype "passive"))
      (node (ref "C55") (pin "1") (pinfunction "1_1") (pintype "passive"))
      (node (ref "C56") (pin "1") (pinfunction "1_1") (pintype "passive"))
      (node (ref "C57") (pin "1") (pinfunction "1_1") (pintype "passive"))
      (node (ref "C58") (pin "1") (pinfunction "1_1") (pintype "passive"))
      (node (ref "C59") (pin "1") (pinfunction "1_1") (pintype "passive"))
      (node (ref "C6") (pin "2") (pinfunction "2_2") (pintype "passive"))
      (node (ref "C61") (pin "2") (pinfunction "2_2") (pintype "passive"))
      (node (ref "C62") (pin "1") (pinfunction "1_1") (pintype "passive"))
      (node (ref "C7") (pin "2") (pinfunction "2_2") (pintype "passive"))
      (node (ref "C72") (pin "2") (pinfunction "2_2") (pintype "passive"))
      (node (ref "C73") (pin "2") (pinfunction "2_2") (pintype "passive"))
      (node (ref "C74") (pin "2") (pinfunction "2_2") (pintype "passive"))
      (node (ref "C75") (pin "2") (pinfunction "2_2") (pintype "passive"))
      (node (ref "C8") (pin "1") (pinfunction "1_1") (pintype "passive"))
      (node (ref "J15") (pin "1") (pinfunction "1_1") (pintype "passive"))
      (node (ref "J20") (pin "1") (pinfunction "1_1") (pintype "passive"))
      (node (ref "J21") (pin "2") (pinfunction "2_2") (pintype "passive"))
      (node (ref "J22") (pin "2") (pinfunction "2_2") (pintype "passive"))
      (node (ref "J3") (pin "1") (pinfunction "1_1") (pintype "passive"))
      (node (ref "J3") (pin "2") (pinfunction "2_2") (pintype "passive"))
      (node (ref "MH1") (pin "1") (pinfunction "GND_1") (pintype "passive"))
      (node (ref "MH2") (pin "1") (pinfunction "GND_1") (pintype "passive"))
      (node (ref "MH3") (pin "1") (pinfunction "GND_1") (pintype "passive"))
      (node (ref "MH4") (pin "1") (pinfunction "GND_1") (pintype "passive"))
      (node (ref "PGND1") (pin "1") (pinfunction "1_1") (pintype "passive"))
      (node (ref "PGND2") (pin "1") (pinfunction "1_1") (pintype "passive"))
      (node (ref "PGND3") (pin "1") (pinfunction "1_1") (pintype "passive"))
      (node (ref "R1") (pin "2") (pinfunction "2_2") (pintype "passive"))
      (node (ref "R20") (pin "1") (pinfunction "1_1") (pintype "passive"))
      (node (ref "R22") (pin "1") (pinfunction "1_1") (pintype "passive"))
      (node (ref "R23") (pin "1") (pinfunction "1_1") (pintype "passive"))
      (node (ref "R24") (pin "1") (pinfunction "1_1") (pintype "passive"))
      (node (ref "R25") (pin "1") (pinfunction "1_1") (pintype "passive"))
      (node (ref "R26") (pin "1") (pinfunction "1_1") (pintype "passive"))
      (node (ref "R27") (pin "1") (pinfunction "1_1") (pintype "passive"))
      (node (ref "R28") (pin "1") (pinfunction "1_1") (pintype "passive"))
      (node (ref "R29") (pin "1") (pinfunction "1_1") (pintype "passive"))
      (node (ref "R30") (pin "1") (pinfunction "1_1") (pintype "passive"))
      (node (ref "R31") (pin "1") (pinfunction "1_1") (pintype "passive"))
      (node (ref "R33") (pin "1") (pinfunction "1_1") (pintype "passive"))
      (node (ref "R37") (pin "2") (pinfunction "2_2") (pintype "passive"))
      (node (ref "R39") (pin "1") (pinfunction "1_1") (pintype "passive"))
      (node (ref "R49") (pin "1") (pinfunction "1_1") (pintype "passive"))
      (node (ref "R50") (pin "1") (pinfunction "1_1") (pintype "passive"))
      (node (ref "R51") (pin "1") (pinfunction "1_1") (pintype "passive"))
      (node (ref "R52") (pin "1") (pinfunction "1_1") (pintype "passive"))
      (node (ref "R53") (pin "1") (pinfunction "1_1") (pintype "passive"))
      (node (ref "R54") (pin "1") (pinfunction "1_1") (pintype "passive"))
      (node (ref "R55") (pin "1") (pinfunction "1_1") (pintype "passive"))
      (node (ref "R56") (pin "1") (pinfunction "1_1") (pintype "passive"))
      (node (ref "R57") (pin "1") (pinfunction "1_1") (pintype "passive"))
      (node (ref "R58") (pin "1") (pinfunction "1_1") (pintype "passive"))
      (node (ref "U5") (pin "1") (pinfunction "GND_1") (pintype "passive"))
      (node (ref "U6") (pin "13") (pinfunction "VS-_13") (pintype "power_in"))
      (node (ref "U6") (pin "14") (pinfunction "VS-_14") (pintype "power_in"))
      (node (ref "U6") (pin "15") (pinfunction "VS-_15") (pintype "power_in"))
      (node (ref "U6") (pin "16") (pinfunction "VS-_16") (pintype "power_in"))
      (node (ref "U6") (pin "17") (pinfunction "EP_17") (pintype "power_in"))
    )
    (net (code "46") (name "VBUS") (class "Default")
      (node (ref "C1") (pin "1") (pinfunction "1_1") (pintype "passive"))
      (node (ref "C2") (pin "1") (pinfunction "1_1") (pintype "passive"))
      (node (ref "C3") (pin "1") (pinfunction "1_1") (pintype "passive"))
      (node (ref "C4") (pin "1") (pinfunction "1_1") (pintype "passive"))
      (node (ref "C6") (pin "1") (pinfunction "1_1") (pintype "passive"))
      (node (ref "C7") (pin "1") (pinfunction "1_1") (pintype "passive"))
      (node (ref "C72") (pin "1") (pinfunction "1_1") (pintype "passive"))
      (node (ref "C73") (pin "1") (pinfunction "1_1") (pintype "passive"))
      (node (ref "C74") (pin "1") (pinfunction "1_1") (pintype "passive"))
      (node (ref "C75") (pin "1") (pinfunction "1_1") (pintype "passive"))
      (node (ref "G1") (pin "4") (pinfunction "D_4") (pintype "passive"))
      (node (ref "J1") (pin "1") (pinfunction "1_1") (pintype "passive"))
      (node (ref "J1") (pin "2") (pinfunction "2_2") (pintype "passive"))
      (node (ref "J2") (pin "1") (pinfunction "1_1") (pintype "passive"))
      (node (ref "R1") (pin "1") (pinfunction "1_1") (pintype "passive"))
      (node (ref "Vdd1") (pin "1") (pinfunction "1_1") (pintype "passive"))
    )
    (net (code "47") (name "unconnected-(MH7-GND-Pad1)") (class "Default")
      (node (ref "MH7") (pin "1") (pinfunction "GND_1") (pintype "passive+no_connect"))
    )
    (net (code "48") (name "unconnected-(MH8-GND-Pad1)") (class "Default")
      (node (ref "MH8") (pin "1") (pinfunction "GND_1") (pintype "passive+no_connect"))
    )
  )
)
